# nomad.net
KiCad netlist of a schematic drawn in EAGLE
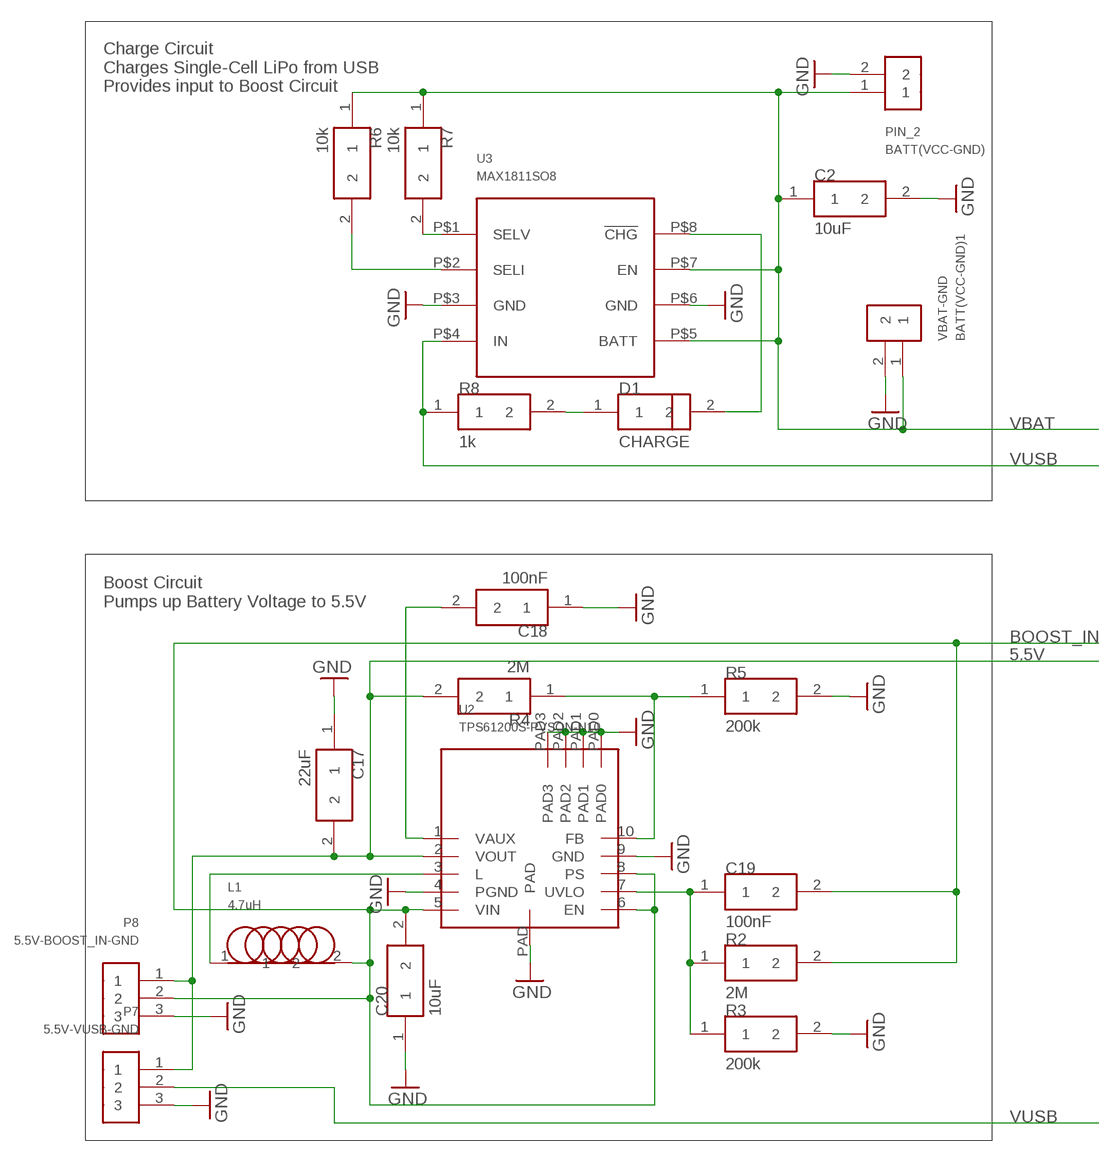
[diagram p0: schematic, sheet 1]

(export (version "E")
  (design (tool "Eeschema 10.0.6"))
  (components
    (comp (ref "BATT(VCC-GND)")
      (value "PIN_2")
      (footprint "eagle-import:PIN_2")
      (libsource (lib "eagle-import") (part "PIN_2"))
    )
    (comp (ref "BATT(VCC-GND)1")
      (value "VBAT-GND")
      (footprint "eagle-import:PIN_2")
      (libsource (lib "eagle-import") (part "PIN_2"))
    )
    (comp (ref "C2")
      (value "10uF")
      (footprint "eagle-import:0805")
      (libsource (lib "eagle-import") (part "CAP0805"))
    )
    (comp (ref "C17")
      (value "22uF")
      (footprint "eagle-import:1206")
      (libsource (lib "eagle-import") (part "CAP1206"))
    )
    (comp (ref "C18")
      (value "100nF")
      (footprint "eagle-import:0805")
      (libsource (lib "eagle-import") (part "CAP0805"))
    )
    (comp (ref "C19")
      (value "100nF")
      (footprint "eagle-import:0805")
      (libsource (lib "eagle-import") (part "CAP0805"))
    )
    (comp (ref "C20")
      (value "10uF")
      (footprint "eagle-import:0805")
      (libsource (lib "eagle-import") (part "CAP0805"))
    )
    (comp (ref "D1")
      (value "CHARGE")
      (footprint "eagle-import:0805")
      (libsource (lib "eagle-import") (part "LED0805"))
    )
    (comp (ref "L1")
      (value "4.7uH")
      (footprint "eagle-import:IND-SMD-3232")
      (libsource (lib "eagle-import") (part "INDSMD-3232"))
    )
    (comp (ref "P7")
      (value "5.5V-VUSB-GND")
      (footprint "eagle-import:PIN_3")
      (libsource (lib "eagle-import") (part "PIN_3"))
    )
    (comp (ref "P8")
      (value "5.5V-BOOST_IN-GND")
      (footprint "eagle-import:PIN_3")
      (libsource (lib "eagle-import") (part "PIN_3"))
    )
    (comp (ref "R2")
      (value "2M")
      (footprint "eagle-import:0805")
      (libsource (lib "eagle-import") (part "RES0805"))
    )
    (comp (ref "R3")
      (value "200k")
      (footprint "eagle-import:0805")
      (libsource (lib "eagle-import") (part "RES0805"))
    )
    (comp (ref "R4")
      (value "2M")
      (footprint "eagle-import:0805")
      (libsource (lib "eagle-import") (part "RES0805"))
    )
    (comp (ref "R5")
      (value "200k")
      (footprint "eagle-import:0805")
      (libsource (lib "eagle-import") (part "RES0805"))
    )
    (comp (ref "R6")
      (value "10k")
      (footprint "eagle-import:0805")
      (libsource (lib "eagle-import") (part "RES0805"))
    )
    (comp (ref "R7")
      (value "10k")
      (footprint "eagle-import:0805")
      (libsource (lib "eagle-import") (part "RES0805"))
    )
    (comp (ref "R8")
      (value "1k")
      (footprint "eagle-import:0805")
      (libsource (lib "eagle-import") (part "RES0805"))
    )
    (comp (ref "U2")
      (value "TPS61200S-PVSON-N10")
      (footprint "eagle-import:S-PVSON-N10")
      (libsource (lib "eagle-import") (part "TPS61200S-PVSON-N10"))
    )
    (comp (ref "U3")
      (value "MAX1811SO8")
      (footprint "eagle-import:SO8")
      (libsource (lib "eagle-import") (part "MAX1811SO8"))
    )
  )
  (nets
    (net (code "1") (name "/5.5V") (class "Default")
      (node (ref "C17") (pin "2") (pinfunction "2_2") (pintype "bidirectional"))
      (node (ref "P7") (pin "1") (pinfunction "1_1") (pintype "bidirectional"))
      (node (ref "P8") (pin "1") (pinfunction "1_1") (pintype "bidirectional"))
      (node (ref "R4") (pin "2") (pinfunction "2_2") (pintype "bidirectional"))
      (node (ref "U2") (pin "2") (pinfunction "VOUT_2") (pintype "bidirectional"))
    )
    (net (code "2") (name "/BOOST_IN") (class "Default")
      (node (ref "C19") (pin "2") (pinfunction "2_2") (pintype "bidirectional"))
      (node (ref "C20") (pin "2") (pinfunction "2_2") (pintype "bidirectional"))
      (node (ref "L1") (pin "2") (pinfunction "2_2") (pintype "bidirectional"))
      (node (ref "P8") (pin "2") (pinfunction "2_2") (pintype "bidirectional"))
      (node (ref "R2") (pin "2") (pinfunction "2_2") (pintype "bidirectional"))
      (node (ref "U2") (pin "5") (pinfunction "VIN_5") (pintype "bidirectional"))
      (node (ref "U2") (pin "6") (pinfunction "EN_6") (pintype "bidirectional"))
      (node (ref "U2") (pin "8") (pinfunction "PS_8") (pintype "bidirectional"))
    )
    (net (code "3") (name "/VBAT") (class "Default")
      (node (ref "BATT(VCC-GND)") (pin "1") (pinfunction "1_1") (pintype "bidirectional"))
      (node (ref "BATT(VCC-GND)1") (pin "1") (pinfunction "1_1") (pintype "bidirectional"))
      (node (ref "C2") (pin "1") (pinfunction "1_1") (pintype "bidirectional"))
      (node (ref "R6") (pin "1") (pinfunction "1_1") (pintype "bidirectional"))
      (node (ref "R7") (pin "1") (pinfunction "1_1") (pintype "bidirectional"))
      (node (ref "U3") (pin "P$5") (pinfunction "BATT_P$5") (pintype "bidirectional"))
      (node (ref "U3") (pin "P$7") (pinfunction "EN_P$7") (pintype "bidirectional"))
    )
    (net (code "4") (name "/VUSB") (class "Default")
      (node (ref "P7") (pin "2") (pinfunction "2_2") (pintype "bidirectional"))
      (node (ref "R8") (pin "1") (pinfunction "1_1") (pintype "bidirectional"))
      (node (ref "U3") (pin "P$4") (pinfunction "IN_P$4") (pintype "bidirectional"))
    )
    (net (code "5") (name "GND") (class "Default")
      (node (ref "BATT(VCC-GND)") (pin "2") (pinfunction "2_2") (pintype "bidirectional"))
      (node (ref "BATT(VCC-GND)1") (pin "2") (pinfunction "2_2") (pintype "bidirectional"))
      (node (ref "C17") (pin "1") (pinfunction "1_1") (pintype "bidirectional"))
      (node (ref "C18") (pin "1") (pinfunction "1_1") (pintype "bidirectional"))
      (node (ref "C2") (pin "2") (pinfunction "2_2") (pintype "bidirectional"))
      (node (ref "C20") (pin "1") (pinfunction "1_1") (pintype "bidirectional"))
      (node (ref "P7") (pin "3") (pinfunction "3_3") (pintype "bidirectional"))
      (node (ref "P8") (pin "3") (pinfunction "3_3") (pintype "bidirectional"))
      (node (ref "R3") (pin "2") (pinfunction "2_2") (pintype "bidirectional"))
      (node (ref "R5") (pin "2") (pinfunction "2_2") (pintype "bidirectional"))
      (node (ref "U2") (pin "4") (pinfunction "PGND_4") (pintype "bidirectional"))
      (node (ref "U2") (pin "9") (pinfunction "GND_9") (pintype "bidirectional"))
      (node (ref "U2") (pin "PAD") (pinfunction "PAD_PAD") (pintype "bidirectional"))
      (node (ref "U2") (pin "PAD0") (pinfunction "PAD0_PAD0") (pintype "bidirectional"))
      (node (ref "U2") (pin "PAD1") (pinfunction "PAD1_PAD1") (pintype "bidirectional"))
      (node (ref "U2") (pin "PAD2") (pinfunction "PAD2_PAD2") (pintype "bidirectional"))
      (node (ref "U2") (pin "PAD3") (pinfunction "PAD3_PAD3") (pintype "bidirectional"))
      (node (ref "U3") (pin "P$3") (pinfunction "GND_P$3") (pintype "bidirectional"))
      (node (ref "U3") (pin "P$6") (pinfunction "GND_P$6") (pintype "bidirectional"))
    )
    (net (code "6") (name "Net-(D1-Pad1)") (class "Default")
      (node (ref "D1") (pin "1") (pinfunction "1_1") (pintype "bidirectional"))
      (node (ref "R8") (pin "2") (pinfunction "2_2") (pintype "bidirectional"))
    )
    (net (code "7") (name "Net-(U2-FB)") (class "Default")
      (node (ref "R4") (pin "1") (pinfunction "1_1") (pintype "bidirectional"))
      (node (ref "R5") (pin "1") (pinfunction "1_1") (pintype "bidirectional"))
      (node (ref "U2") (pin "10") (pinfunction "FB_10") (pintype "bidirectional"))
    )
    (net (code "8") (name "Net-(U2-L)") (class "Default")
      (node (ref "L1") (pin "1") (pinfunction "1_1") (pintype "bidirectional"))
      (node (ref "U2") (pin "3") (pinfunction "L_3") (pintype "bidirectional"))
    )
    (net (code "9") (name "Net-(U2-UVLO)") (class "Default")
      (node (ref "C19") (pin "1") (pinfunction "1_1") (pintype "bidirectional"))
      (node (ref "R2") (pin "1") (pinfunction "1_1") (pintype "bidirectional"))
      (node (ref "R3") (pin "1") (pinfunction "1_1") (pintype "bidirectional"))
      (node (ref "U2") (pin "7") (pinfunction "UVLO_7") (pintype "bidirectional"))
    )
    (net (code "10") (name "Net-(U2-VAUX)") (class "Default")
      (node (ref "C18") (pin "2") (pinfunction "2_2") (pintype "bidirectional"))
      (node (ref "U2") (pin "1") (pinfunction "VAUX_1") (pintype "bidirectional"))
    )
    (net (code "11") (name "Net-(U3-SELI)") (class "Default")
      (node (ref "R6") (pin "2") (pinfunction "2_2") (pintype "bidirectional"))
      (node (ref "U3") (pin "P$2") (pinfunction "SELI_P$2") (pintype "bidirectional"))
    )
    (net (code "12") (name "Net-(U3-SELV)") (class "Default")
      (node (ref "R7") (pin "2") (pinfunction "2_2") (pintype "bidirectional"))
      (node (ref "U3") (pin "P$1") (pinfunction "SELV_P$1") (pintype "bidirectional"))
    )
    (net (code "13") (name "Net-(U3-~{CHG})") (class "Default")
      (node (ref "D1") (pin "2") (pinfunction "2_2") (pintype "bidirectional"))
      (node (ref "U3") (pin "P$8") (pinfunction "~{CHG}_P$8") (pintype "bidirectional"))
    )
  )
)
